# colorround.net
KiCad netlist of a schematic drawn in EAGLE
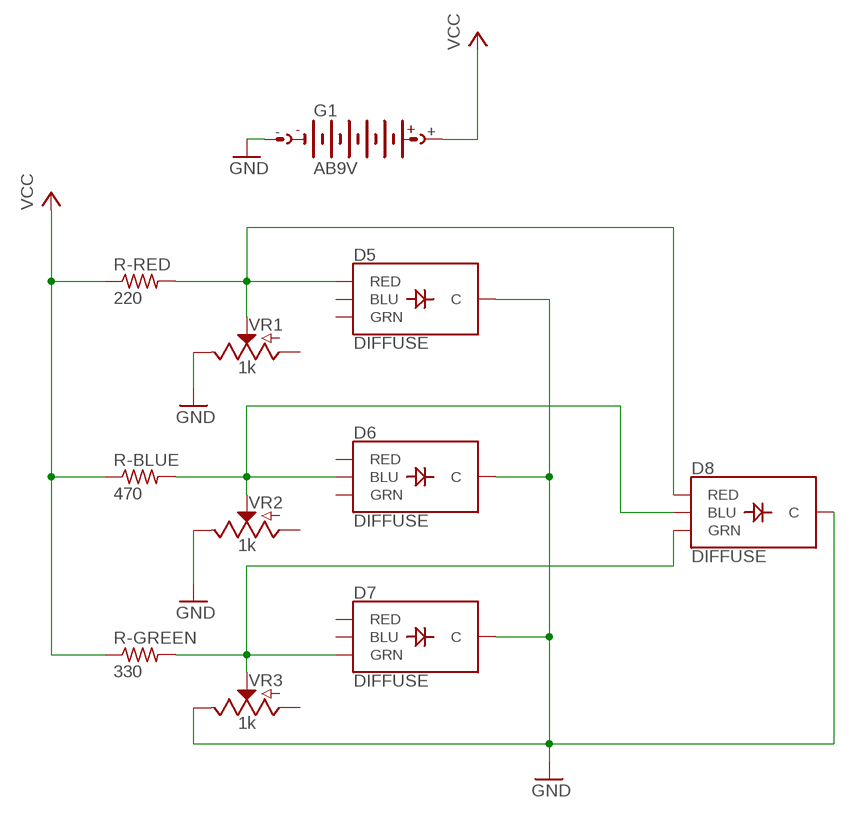
[diagram p0: schematic, sheet 1]

(export (version "E")
  (design (tool "Eeschema 10.0.6"))
  (components
    (comp (ref "D5")
      (value "DIFFUSE")
      (footprint "eagle-import:LED-RGB-THRU")
      (libsource (lib "eagle-import") (part "LED-RGB-CCDIFFUSE"))
    )
    (comp (ref "D6")
      (value "DIFFUSE")
      (footprint "eagle-import:LED-RGB-THRU")
      (libsource (lib "eagle-import") (part "LED-RGB-CCDIFFUSE"))
    )
    (comp (ref "D7")
      (value "DIFFUSE")
      (footprint "eagle-import:LED-RGB-THRU")
      (libsource (lib "eagle-import") (part "LED-RGB-CCDIFFUSE"))
    )
    (comp (ref "D8")
      (value "DIFFUSE")
      (footprint "eagle-import:LED-RGB-THRU")
      (libsource (lib "eagle-import") (part "LED-RGB-CCDIFFUSE"))
    )
    (comp (ref "G1")
      (value "AB9V")
      (footprint "eagle-import:AB9V")
      (libsource (lib "eagle-import") (part "AB9V"))
    )
    (comp (ref "R-BLUE")
      (value "470")
      (footprint "eagle-import:0207_10")
      (libsource (lib "eagle-import") (part "R-US_0207/10"))
    )
    (comp (ref "R-GREEN")
      (value "330")
      (footprint "eagle-import:0207_10")
      (libsource (lib "eagle-import") (part "R-US_0207/10"))
    )
    (comp (ref "R-RED")
      (value "220")
      (footprint "eagle-import:0207_10")
      (libsource (lib "eagle-import") (part "R-US_0207/10"))
    )
    (comp (ref "VR1")
      (value "1k")
      (footprint "eagle-import:POT-PTH-ALPS")
      (libsource (lib "eagle-import") (part "POTENTIOMETER-PTH-9MM-1/20W-20%"))
    )
    (comp (ref "VR2")
      (value "1k")
      (footprint "eagle-import:POT-PTH-ALPS")
      (libsource (lib "eagle-import") (part "POTENTIOMETER-PTH-9MM-1/20W-20%"))
    )
    (comp (ref "VR3")
      (value "1k")
      (footprint "eagle-import:POT-PTH-ALPS")
      (libsource (lib "eagle-import") (part "POTENTIOMETER-PTH-9MM-1/20W-20%"))
    )
  )
  (nets
    (net (code "1") (name "GND") (class "Default")
      (node (ref "D5") (pin "2") (pinfunction "C_2") (pintype "bidirectional"))
      (node (ref "D6") (pin "2") (pinfunction "C_2") (pintype "bidirectional"))
      (node (ref "D7") (pin "2") (pinfunction "C_2") (pintype "bidirectional"))
      (node (ref "D8") (pin "2") (pinfunction "C_2") (pintype "bidirectional"))
      (node (ref "G1") (pin "-") (pinfunction "-_-") (pintype "passive"))
      (node (ref "VR1") (pin "P$1") (pinfunction "E_P$1") (pintype "passive"))
      (node (ref "VR2") (pin "P$1") (pinfunction "E_P$1") (pintype "passive"))
      (node (ref "VR3") (pin "P$1") (pinfunction "E_P$1") (pintype "passive"))
    )
    (net (code "2") (name "Net-(D5-RED)") (class "Default")
      (node (ref "D5") (pin "1") (pinfunction "RED_1") (pintype "bidirectional"))
      (node (ref "D8") (pin "1") (pinfunction "RED_1") (pintype "bidirectional"))
      (node (ref "R-RED") (pin "2") (pinfunction "2_2") (pintype "passive"))
      (node (ref "VR1") (pin "P$2") (pinfunction "S_P$2") (pintype "passive"))
    )
    (net (code "3") (name "Net-(D6-BLU)") (class "Default")
      (node (ref "D6") (pin "4") (pinfunction "BLU_4") (pintype "bidirectional"))
      (node (ref "D8") (pin "4") (pinfunction "BLU_4") (pintype "bidirectional"))
      (node (ref "R-BLUE") (pin "2") (pinfunction "2_2") (pintype "passive"))
      (node (ref "VR2") (pin "P$2") (pinfunction "S_P$2") (pintype "passive"))
    )
    (net (code "4") (name "Net-(D7-GRN)") (class "Default")
      (node (ref "D7") (pin "3") (pinfunction "GRN_3") (pintype "bidirectional"))
      (node (ref "D8") (pin "3") (pinfunction "GRN_3") (pintype "bidirectional"))
      (node (ref "R-GREEN") (pin "2") (pinfunction "2_2") (pintype "passive"))
      (node (ref "VR3") (pin "P$2") (pinfunction "S_P$2") (pintype "passive"))
    )
    (net (code "5") (name "VCC") (class "Default")
      (node (ref "G1") (pin "+") (pinfunction "+_+") (pintype "passive"))
      (node (ref "R-BLUE") (pin "1") (pinfunction "1_1") (pintype "passive"))
      (node (ref "R-GREEN") (pin "1") (pinfunction "1_1") (pintype "passive"))
      (node (ref "R-RED") (pin "1") (pinfunction "1_1") (pintype "passive"))
    )
    (net (code "6") (name "unconnected-(D5-BLU-Pad4)") (class "Default")
      (node (ref "D5") (pin "4") (pinfunction "BLU_4") (pintype "bidirectional"))
    )
    (net (code "7") (name "unconnected-(D5-GRN-Pad3)") (class "Default")
      (node (ref "D5") (pin "3") (pinfunction "GRN_3") (pintype "bidirectional"))
    )
    (net (code "8") (name "unconnected-(D6-GRN-Pad3)") (class "Default")
      (node (ref "D6") (pin "3") (pinfunction "GRN_3") (pintype "bidirectional"))
    )
    (net (code "9") (name "unconnected-(D6-RED-Pad1)") (class "Default")
      (node (ref "D6") (pin "1") (pinfunction "RED_1") (pintype "bidirectional"))
    )
    (net (code "10") (name "unconnected-(D7-BLU-Pad4)") (class "Default")
      (node (ref "D7") (pin "4") (pinfunction "BLU_4") (pintype "bidirectional"))
    )
    (net (code "11") (name "unconnected-(D7-RED-Pad1)") (class "Default")
      (node (ref "D7") (pin "1") (pinfunction "RED_1") (pintype "bidirectional"))
    )
    (net (code "12") (name "unconnected-(VR1-A-PadP$3)") (class "Default")
      (node (ref "VR1") (pin "P$3") (pinfunction "A_P$3") (pintype "passive"))
    )
    (net (code "13") (name "unconnected-(VR2-A-PadP$3)") (class "Default")
      (node (ref "VR2") (pin "P$3") (pinfunction "A_P$3") (pintype "passive"))
    )
    (net (code "14") (name "unconnected-(VR3-A-PadP$3)") (class "Default")
      (node (ref "VR3") (pin "P$3") (pinfunction "A_P$3") (pintype "passive"))
    )
  )
)
